# Controller.net
KiCad netlist of a schematic drawn in EAGLE
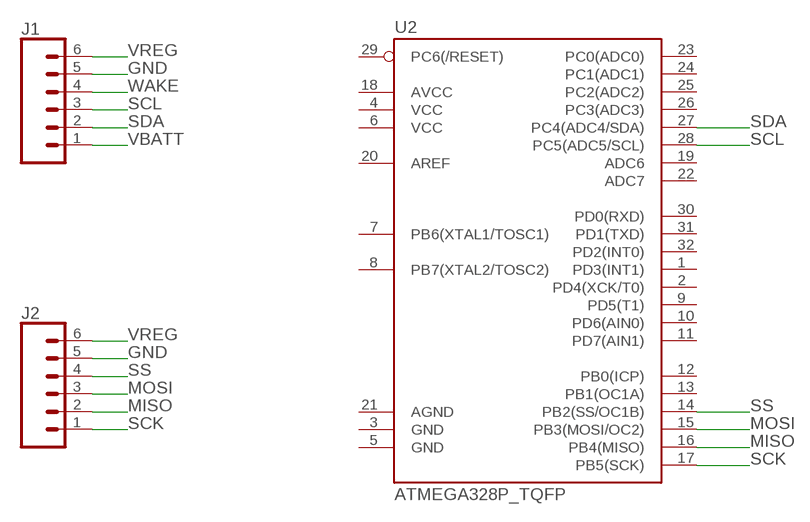
[diagram p0: schematic, sheet 1]

(export (version "E")
  (design (tool "Eeschema 10.0.6"))
  (components
    (comp (ref "J1")
      (value "CONN_06LOCK_LONGPADS")
      (footprint "eagle-import:1X06_LOCK_LONGPADS")
      (libsource (lib "eagle-import") (part "CONN_06LOCK_LONGPADS"))
    )
    (comp (ref "J2")
      (value "CONN_06LOCK_LONGPADS")
      (footprint "eagle-import:1X06_LOCK_LONGPADS")
      (libsource (lib "eagle-import") (part "CONN_06LOCK_LONGPADS"))
    )
    (comp (ref "U2")
      (value "ATMEGA328P_TQFP")
      (footprint "eagle-import:TQFP32-08")
      (libsource (lib "eagle-import") (part "ATMEGA328P_TQFP"))
    )
  )
  (nets
    (net (code "1") (name "/GND") (class "Default")
      (node (ref "J1") (pin "5") (pinfunction "5_5") (pintype "passive"))
      (node (ref "J2") (pin "5") (pinfunction "5_5") (pintype "passive"))
    )
    (net (code "2") (name "/MISO") (class "Default")
      (node (ref "J2") (pin "2") (pinfunction "2_2") (pintype "passive"))
      (node (ref "U2") (pin "16") (pinfunction "PB4(MISO)_16") (pintype "bidirectional"))
    )
    (net (code "3") (name "/MOSI") (class "Default")
      (node (ref "J2") (pin "3") (pinfunction "3_3") (pintype "passive"))
      (node (ref "U2") (pin "15") (pinfunction "PB3(MOSI/OC2)_15") (pintype "bidirectional"))
    )
    (net (code "4") (name "/SCK") (class "Default")
      (node (ref "J2") (pin "1") (pinfunction "1_1") (pintype "passive"))
      (node (ref "U2") (pin "17") (pinfunction "PB5(SCK)_17") (pintype "bidirectional"))
    )
    (net (code "5") (name "/SCL") (class "Default")
      (node (ref "J1") (pin "3") (pinfunction "3_3") (pintype "passive"))
      (node (ref "U2") (pin "28") (pinfunction "PC5(ADC5/SCL)_28") (pintype "bidirectional"))
    )
    (net (code "6") (name "/SDA") (class "Default")
      (node (ref "J1") (pin "2") (pinfunction "2_2") (pintype "passive"))
      (node (ref "U2") (pin "27") (pinfunction "PC4(ADC4/SDA)_27") (pintype "bidirectional"))
    )
    (net (code "7") (name "/SS") (class "Default")
      (node (ref "J2") (pin "4") (pinfunction "4_4") (pintype "passive"))
      (node (ref "U2") (pin "14") (pinfunction "PB2(SS/OC1B)_14") (pintype "bidirectional"))
    )
    (net (code "8") (name "/VBATT") (class "Default")
      (node (ref "J1") (pin "1") (pinfunction "1_1") (pintype "passive"))
    )
    (net (code "9") (name "/VREG") (class "Default")
      (node (ref "J1") (pin "6") (pinfunction "6_6") (pintype "passive"))
      (node (ref "J2") (pin "6") (pinfunction "6_6") (pintype "passive"))
    )
    (net (code "10") (name "/WAKE") (class "Default")
      (node (ref "J1") (pin "4") (pinfunction "4_4") (pintype "passive"))
    )
    (net (code "11") (name "unconnected-(U2-ADC6-Pad19)") (class "Default")
      (node (ref "U2") (pin "19") (pinfunction "ADC6_19") (pintype "bidirectional"))
    )
    (net (code "12") (name "unconnected-(U2-ADC7-Pad22)") (class "Default")
      (node (ref "U2") (pin "22") (pinfunction "ADC7_22") (pintype "bidirectional"))
    )
    (net (code "13") (name "unconnected-(U2-AGND-Pad21)") (class "Default")
      (node (ref "U2") (pin "21") (pinfunction "AGND_21") (pintype "bidirectional"))
    )
    (net (code "14") (name "unconnected-(U2-AREF-Pad20)") (class "Default")
      (node (ref "U2") (pin "20") (pinfunction "AREF_20") (pintype "bidirectional"))
    )
    (net (code "15") (name "unconnected-(U2-AVCC-Pad18)") (class "Default")
      (node (ref "U2") (pin "18") (pinfunction "AVCC_18") (pintype "bidirectional"))
    )
    (net (code "16") (name "unconnected-(U2-GND-Pad3)") (class "Default")
      (node (ref "U2") (pin "3") (pinfunction "GND_3") (pintype "bidirectional"))
    )
    (net (code "17") (name "unconnected-(U2-GND-Pad5)") (class "Default")
      (node (ref "U2") (pin "5") (pinfunction "GND_5") (pintype "bidirectional"))
    )
    (net (code "18") (name "unconnected-(U2-PB0(ICP)-Pad12)") (class "Default")
      (node (ref "U2") (pin "12") (pinfunction "PB0(ICP)_12") (pintype "bidirectional"))
    )
    (net (code "19") (name "unconnected-(U2-PB1(OC1A)-Pad13)") (class "Default")
      (node (ref "U2") (pin "13") (pinfunction "PB1(OC1A)_13") (pintype "bidirectional"))
    )
    (net (code "20") (name "unconnected-(U2-PB6(XTAL1{slash}TOSC1)-Pad7)") (class "Default")
      (node (ref "U2") (pin "7") (pinfunction "PB6(XTAL1/TOSC1)_7") (pintype "bidirectional"))
    )
    (net (code "21") (name "unconnected-(U2-PB7(XTAL2{slash}TOSC2)-Pad8)") (class "Default")
      (node (ref "U2") (pin "8") (pinfunction "PB7(XTAL2/TOSC2)_8") (pintype "bidirectional"))
    )
    (net (code "22") (name "unconnected-(U2-PC0(ADC0)-Pad23)") (class "Default")
      (node (ref "U2") (pin "23") (pinfunction "PC0(ADC0)_23") (pintype "bidirectional"))
    )
    (net (code "23") (name "unconnected-(U2-PC1(ADC1)-Pad24)") (class "Default")
      (node (ref "U2") (pin "24") (pinfunction "PC1(ADC1)_24") (pintype "bidirectional"))
    )
    (net (code "24") (name "unconnected-(U2-PC2(ADC2)-Pad25)") (class "Default")
      (node (ref "U2") (pin "25") (pinfunction "PC2(ADC2)_25") (pintype "bidirectional"))
    )
    (net (code "25") (name "unconnected-(U2-PC3(ADC3)-Pad26)") (class "Default")
      (node (ref "U2") (pin "26") (pinfunction "PC3(ADC3)_26") (pintype "bidirectional"))
    )
    (net (code "26") (name "unconnected-(U2-PC6({slash}RESET)-Pad29)") (class "Default")
      (node (ref "U2") (pin "29") (pinfunction "PC6(/RESET)_29") (pintype "bidirectional"))
    )
    (net (code "27") (name "unconnected-(U2-PD0(RXD)-Pad30)") (class "Default")
      (node (ref "U2") (pin "30") (pinfunction "PD0(RXD)_30") (pintype "bidirectional"))
    )
    (net (code "28") (name "unconnected-(U2-PD1(TXD)-Pad31)") (class "Default")
      (node (ref "U2") (pin "31") (pinfunction "PD1(TXD)_31") (pintype "bidirectional"))
    )
    (net (code "29") (name "unconnected-(U2-PD2(INT0)-Pad32)") (class "Default")
      (node (ref "U2") (pin "32") (pinfunction "PD2(INT0)_32") (pintype "bidirectional"))
    )
    (net (code "30") (name "unconnected-(U2-PD3(INT1)-Pad1)") (class "Default")
      (node (ref "U2") (pin "1") (pinfunction "PD3(INT1)_1") (pintype "bidirectional"))
    )
    (net (code "31") (name "unconnected-(U2-PD4(XCK{slash}T0)-Pad2)") (class "Default")
      (node (ref "U2") (pin "2") (pinfunction "PD4(XCK/T0)_2") (pintype "bidirectional"))
    )
    (net (code "32") (name "unconnected-(U2-PD5(T1)-Pad9)") (class "Default")
      (node (ref "U2") (pin "9") (pinfunction "PD5(T1)_9") (pintype "bidirectional"))
    )
    (net (code "33") (name "unconnected-(U2-PD6(AIN0)-Pad10)") (class "Default")
      (node (ref "U2") (pin "10") (pinfunction "PD6(AIN0)_10") (pintype "bidirectional"))
    )
    (net (code "34") (name "unconnected-(U2-PD7(AIN1)-Pad11)") (class "Default")
      (node (ref "U2") (pin "11") (pinfunction "PD7(AIN1)_11") (pintype "bidirectional"))
    )
    (net (code "35") (name "unconnected-(U2-VCC-Pad4)") (class "Default")
      (node (ref "U2") (pin "4") (pinfunction "VCC_4") (pintype "bidirectional"))
    )
    (net (code "36") (name "unconnected-(U2-VCC-Pad6)") (class "Default")
      (node (ref "U2") (pin "6") (pinfunction "VCC_6") (pintype "bidirectional"))
    )
  )
)
